# Koester_station_adapter.net
KiCad netlist of a schematic drawn in EAGLE
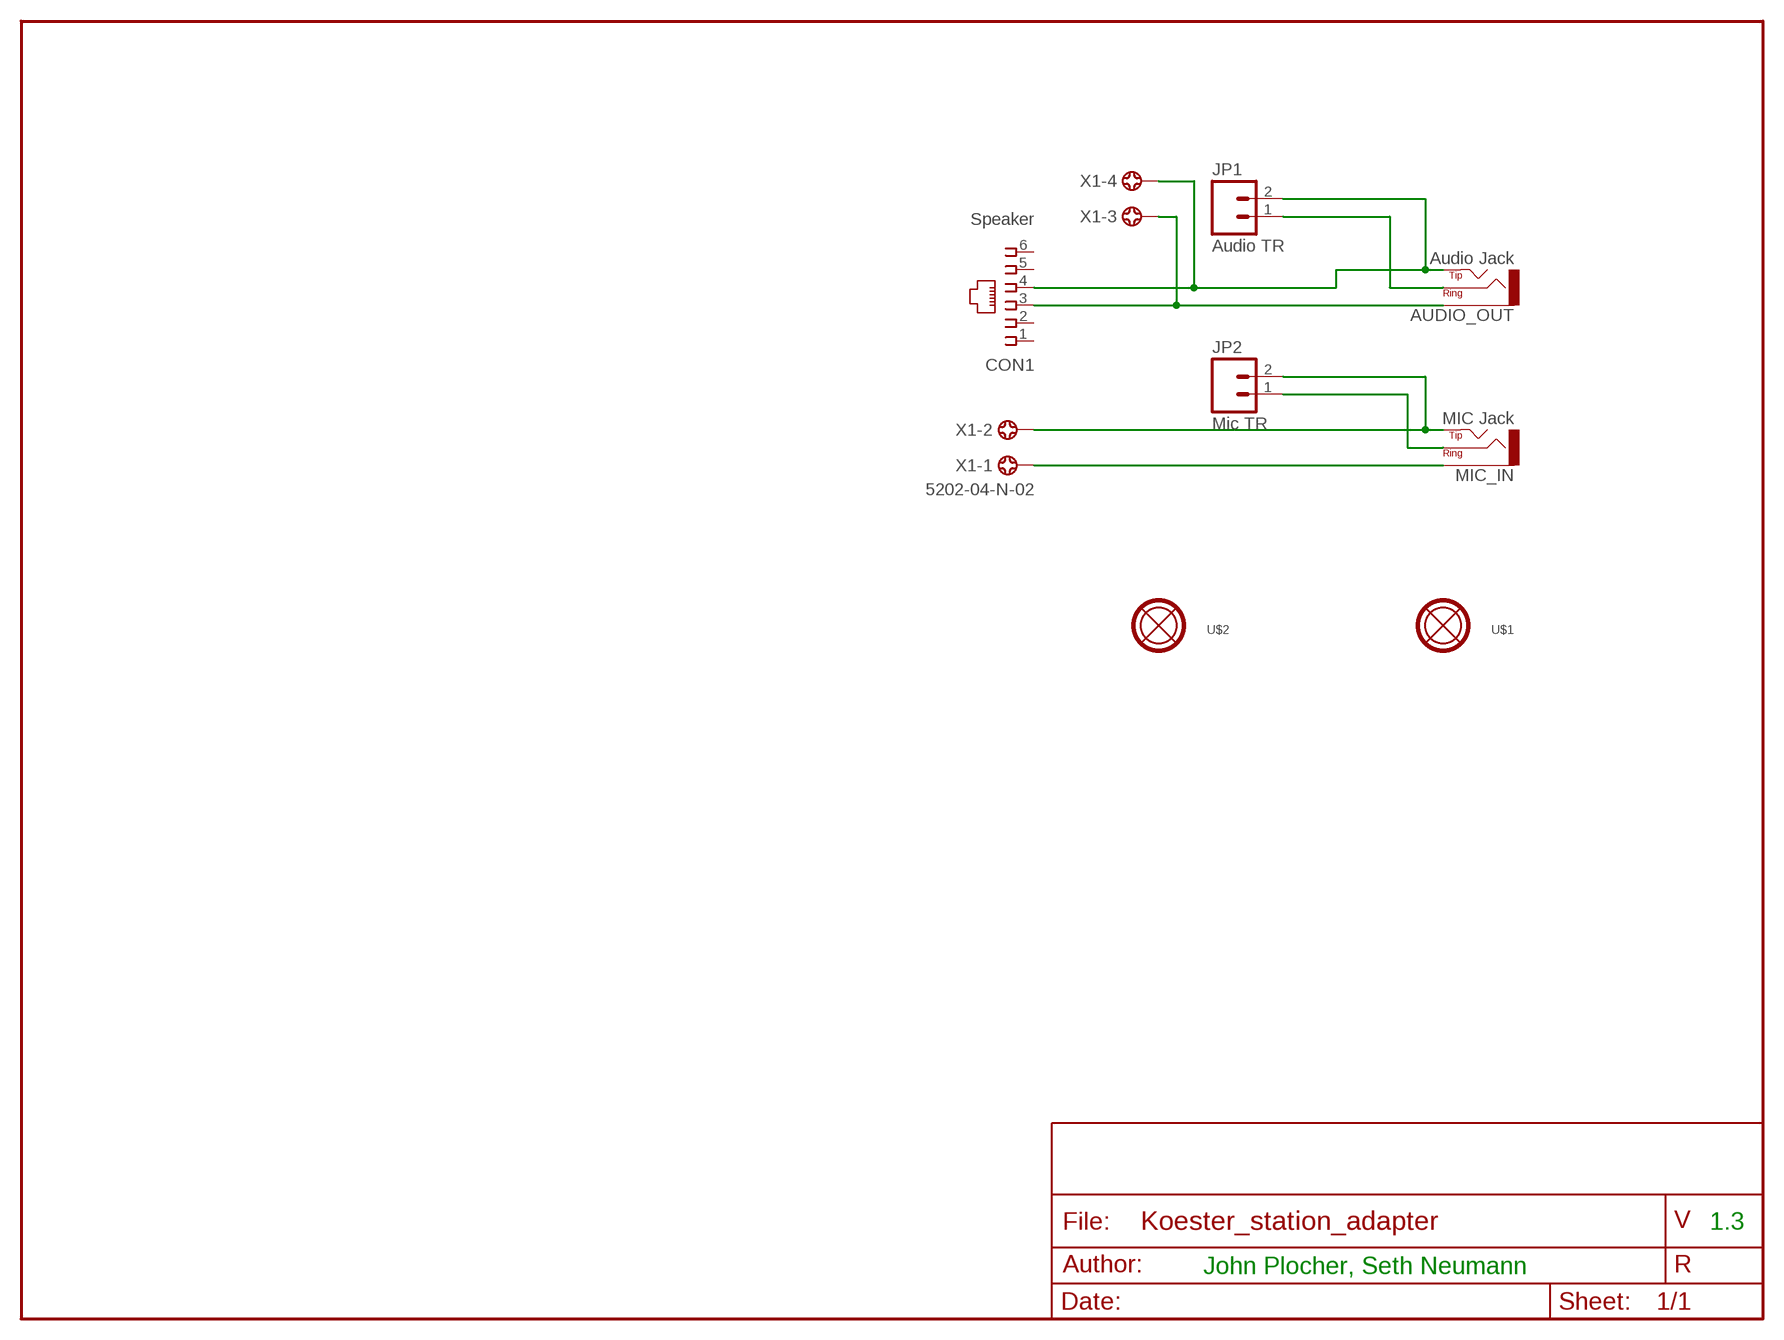
[diagram p0: schematic, sheet 1]

(export (version "E")
  (design (tool "Eeschema 10.0.6"))
  (components
    (comp (ref "AUDIO_OUT")
      (value "Audio Jack")
      (footprint "eagle-import:AUDIO-JACK-3.5MM_STEREO")
      (libsource (lib "eagle-import") (part "CONNECTOR-AUDIO3.5MM-ADAMTECH"))
    )
    (comp (ref "CON1")
      (value "Speaker")
      (footprint "eagle-import:RJ25-INVERTED")
      (libsource (lib "eagle-import") (part "CONNECTOR-RJ25-43860-2-MOLEX"))
    )
    (comp (ref "JP1")
      (value "Audio TR")
      (footprint "eagle-import:MOLEX-1X2_LOCK")
      (libsource (lib "eagle-import") (part "CONNECTOR-M02MOLEX-1X02-LOCK"))
    )
    (comp (ref "JP2")
      (value "Mic TR")
      (footprint "eagle-import:MOLEX-1X2_LOCK")
      (libsource (lib "eagle-import") (part "CONNECTOR-M02MOLEX-1X02-LOCK"))
    )
    (comp (ref "MIC_IN")
      (value "MIC Jack")
      (footprint "eagle-import:AUDIO-JACK-3.5MM_STEREO")
      (libsource (lib "eagle-import") (part "CONNECTOR-AUDIO3.5MM-ADAMTECH"))
    )
    (comp (ref "U$1")
      (value "MOUNTINGHOLE")
      (footprint "eagle-import:MOUNTINGHOLE")
      (libsource (lib "eagle-import") (part "MOUNTINGHOLE"))
    )
    (comp (ref "U$2")
      (value "MOUNTINGHOLE")
      (footprint "eagle-import:MOUNTINGHOLE")
      (libsource (lib "eagle-import") (part "MOUNTINGHOLE"))
    )
    (comp (ref "X1")
      (value "5202-04-N-02")
      (footprint "eagle-import:5202-04-N-02")
      (libsource (lib "eagle-import") (part "5202-04-N-02"))
    )
  )
  (nets
    (net (code "1") (name "Net-(AUDIO_OUT-SLEEVE)") (class "Default")
      (node (ref "AUDIO_OUT") (pin "GND") (pinfunction "SLEEVE_GND") (pintype "bidirectional"))
      (node (ref "CON1") (pin "3") (pinfunction "3_3") (pintype "passive"))
      (node (ref "X1") (pin "3") (pinfunction "1_3") (pintype "passive"))
    )
    (net (code "2") (name "Net-(JP1-A)") (class "Default")
      (node (ref "AUDIO_OUT") (pin "RING") (pinfunction "RING_RING") (pintype "bidirectional"))
      (node (ref "JP1") (pin "1") (pinfunction "A_1") (pintype "passive"))
    )
    (net (code "3") (name "Net-(JP1-B)") (class "Default")
      (node (ref "AUDIO_OUT") (pin "TIP") (pinfunction "TIP_TIP") (pintype "bidirectional"))
      (node (ref "CON1") (pin "4") (pinfunction "4_4") (pintype "passive"))
      (node (ref "JP1") (pin "2") (pinfunction "B_2") (pintype "passive"))
      (node (ref "X1") (pin "4") (pinfunction "1_4") (pintype "passive"))
    )
    (net (code "4") (name "Net-(JP2-A)") (class "Default")
      (node (ref "JP2") (pin "1") (pinfunction "A_1") (pintype "passive"))
      (node (ref "MIC_IN") (pin "RING") (pinfunction "RING_RING") (pintype "bidirectional"))
    )
    (net (code "5") (name "Net-(JP2-B)") (class "Default")
      (node (ref "JP2") (pin "2") (pinfunction "B_2") (pintype "passive"))
      (node (ref "MIC_IN") (pin "TIP") (pinfunction "TIP_TIP") (pintype "bidirectional"))
      (node (ref "X1") (pin "2") (pinfunction "1_2") (pintype "passive"))
    )
    (net (code "6") (name "Net-(MIC_IN-SLEEVE)") (class "Default")
      (node (ref "MIC_IN") (pin "GND") (pinfunction "SLEEVE_GND") (pintype "bidirectional"))
      (node (ref "X1") (pin "1") (pinfunction "1_1") (pintype "passive"))
    )
    (net (code "7") (name "unconnected-(CON1-Pad1)") (class "Default")
      (node (ref "CON1") (pin "1") (pinfunction "1_1") (pintype "passive"))
    )
    (net (code "8") (name "unconnected-(CON1-Pad2)") (class "Default")
      (node (ref "CON1") (pin "2") (pinfunction "2_2") (pintype "passive"))
    )
    (net (code "9") (name "unconnected-(CON1-Pad5)") (class "Default")
      (node (ref "CON1") (pin "5") (pinfunction "5_5") (pintype "passive"))
    )
    (net (code "10") (name "unconnected-(CON1-Pad6)") (class "Default")
      (node (ref "CON1") (pin "6") (pinfunction "6_6") (pintype "passive"))
    )
  )
)
